# WS2812B.net
KiCad netlist of a schematic drawn in Altium Designer
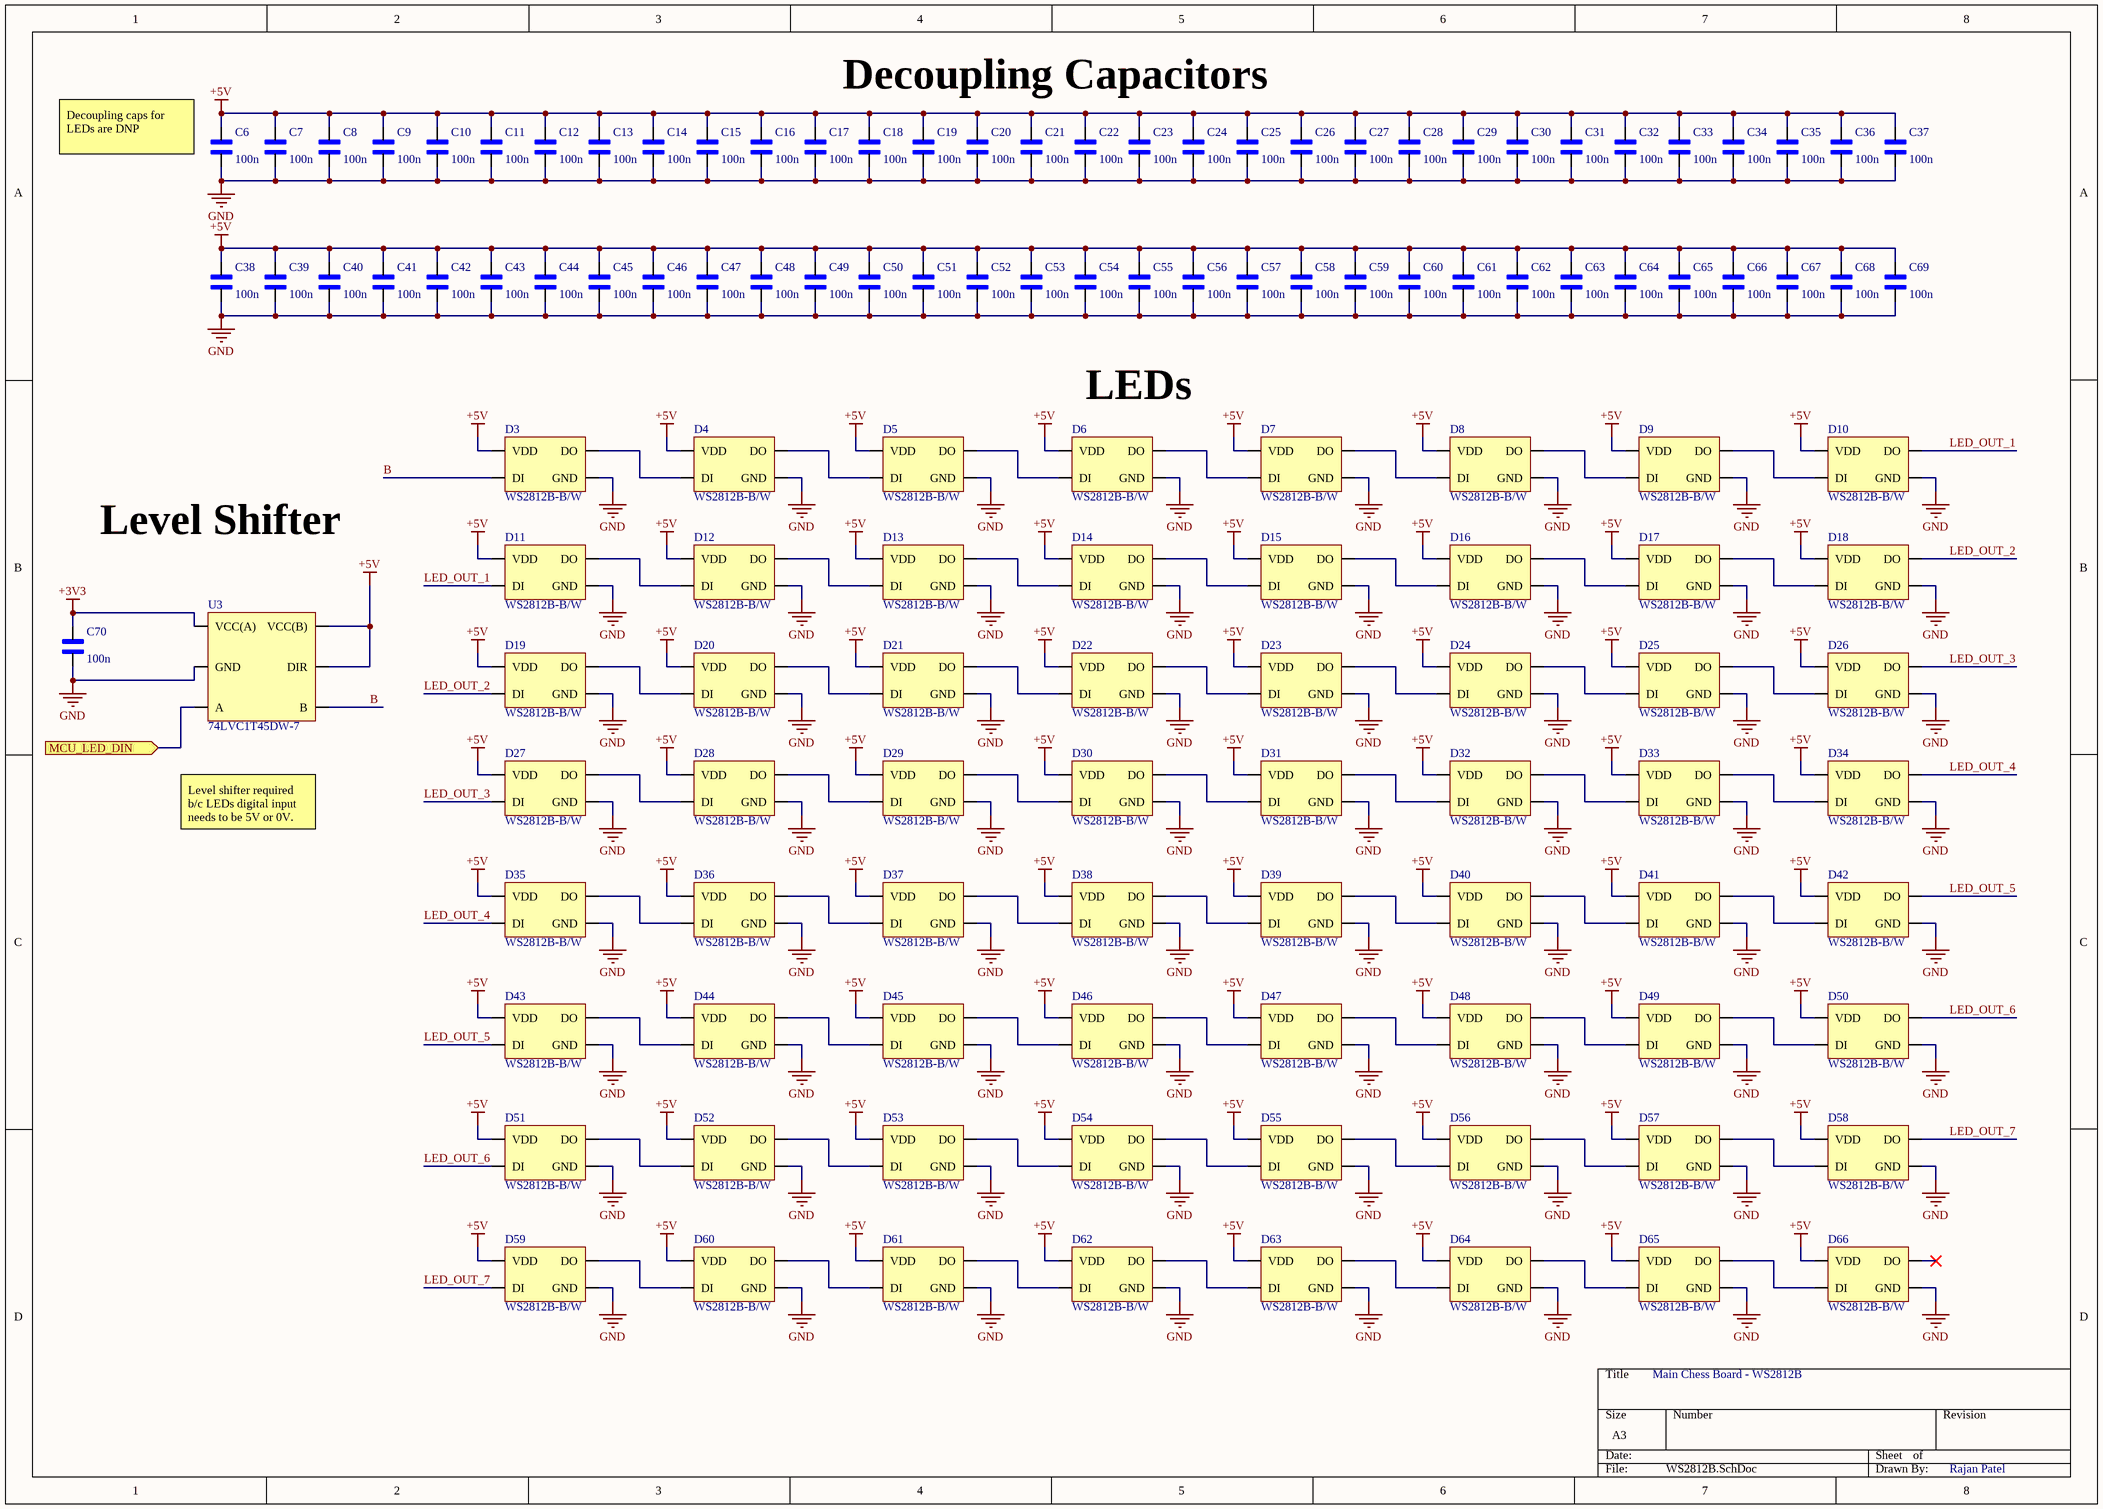
[diagram p0: WS2812B.SchDoc]

(export (version "E")
  (design (tool "Eeschema 10.0.6"))
  (components
    (comp (ref "C6")
      (value "100n")
      (footprint "CAP 0805")
      (libsource (lib "ChessBoardSchLib") (part "CAP 0805"))
    )
    (comp (ref "C7")
      (value "100n")
      (footprint "CAP 0805")
      (libsource (lib "ChessBoardSchLib") (part "CAP 0805"))
    )
    (comp (ref "C8")
      (value "100n")
      (footprint "CAP 0805")
      (libsource (lib "ChessBoardSchLib") (part "CAP 0805"))
    )
    (comp (ref "C9")
      (value "100n")
      (footprint "CAP 0805")
      (libsource (lib "ChessBoardSchLib") (part "CAP 0805"))
    )
    (comp (ref "C10")
      (value "100n")
      (footprint "CAP 0805")
      (libsource (lib "ChessBoardSchLib") (part "CAP 0805"))
    )
    (comp (ref "C11")
      (value "100n")
      (footprint "CAP 0805")
      (libsource (lib "ChessBoardSchLib") (part "CAP 0805"))
    )
    (comp (ref "C12")
      (value "100n")
      (footprint "CAP 0805")
      (libsource (lib "ChessBoardSchLib") (part "CAP 0805"))
    )
    (comp (ref "C13")
      (value "100n")
      (footprint "CAP 0805")
      (libsource (lib "ChessBoardSchLib") (part "CAP 0805"))
    )
    (comp (ref "C14")
      (value "100n")
      (footprint "CAP 0805")
      (libsource (lib "ChessBoardSchLib") (part "CAP 0805"))
    )
    (comp (ref "C15")
      (value "100n")
      (footprint "CAP 0805")
      (libsource (lib "ChessBoardSchLib") (part "CAP 0805"))
    )
    (comp (ref "C16")
      (value "100n")
      (footprint "CAP 0805")
      (libsource (lib "ChessBoardSchLib") (part "CAP 0805"))
    )
    (comp (ref "C17")
      (value "100n")
      (footprint "CAP 0805")
      (libsource (lib "ChessBoardSchLib") (part "CAP 0805"))
    )
    (comp (ref "C18")
      (value "100n")
      (footprint "CAP 0805")
      (libsource (lib "ChessBoardSchLib") (part "CAP 0805"))
    )
    (comp (ref "C19")
      (value "100n")
      (footprint "CAP 0805")
      (libsource (lib "ChessBoardSchLib") (part "CAP 0805"))
    )
    (comp (ref "C20")
      (value "100n")
      (footprint "CAP 0805")
      (libsource (lib "ChessBoardSchLib") (part "CAP 0805"))
    )
    (comp (ref "C21")
      (value "100n")
      (footprint "CAP 0805")
      (libsource (lib "ChessBoardSchLib") (part "CAP 0805"))
    )
    (comp (ref "C22")
      (value "100n")
      (footprint "CAP 0805")
      (libsource (lib "ChessBoardSchLib") (part "CAP 0805"))
    )
    (comp (ref "C23")
      (value "100n")
      (footprint "CAP 0805")
      (libsource (lib "ChessBoardSchLib") (part "CAP 0805"))
    )
    (comp (ref "C24")
      (value "100n")
      (footprint "CAP 0805")
      (libsource (lib "ChessBoardSchLib") (part "CAP 0805"))
    )
    (comp (ref "C25")
      (value "100n")
      (footprint "CAP 0805")
      (libsource (lib "ChessBoardSchLib") (part "CAP 0805"))
    )
    (comp (ref "C26")
      (value "100n")
      (footprint "CAP 0805")
      (libsource (lib "ChessBoardSchLib") (part "CAP 0805"))
    )
    (comp (ref "C27")
      (value "100n")
      (footprint "CAP 0805")
      (libsource (lib "ChessBoardSchLib") (part "CAP 0805"))
    )
    (comp (ref "C28")
      (value "100n")
      (footprint "CAP 0805")
      (libsource (lib "ChessBoardSchLib") (part "CAP 0805"))
    )
    (comp (ref "C29")
      (value "100n")
      (footprint "CAP 0805")
      (libsource (lib "ChessBoardSchLib") (part "CAP 0805"))
    )
    (comp (ref "C30")
      (value "100n")
      (footprint "CAP 0805")
      (libsource (lib "ChessBoardSchLib") (part "CAP 0805"))
    )
    (comp (ref "C31")
      (value "100n")
      (footprint "CAP 0805")
      (libsource (lib "ChessBoardSchLib") (part "CAP 0805"))
    )
    (comp (ref "C32")
      (value "100n")
      (footprint "CAP 0805")
      (libsource (lib "ChessBoardSchLib") (part "CAP 0805"))
    )
    (comp (ref "C33")
      (value "100n")
      (footprint "CAP 0805")
      (libsource (lib "ChessBoardSchLib") (part "CAP 0805"))
    )
    (comp (ref "C34")
      (value "100n")
      (footprint "CAP 0805")
      (libsource (lib "ChessBoardSchLib") (part "CAP 0805"))
    )
    (comp (ref "C35")
      (value "100n")
      (footprint "CAP 0805")
      (libsource (lib "ChessBoardSchLib") (part "CAP 0805"))
    )
    (comp (ref "C36")
      (value "100n")
      (footprint "CAP 0805")
      (libsource (lib "ChessBoardSchLib") (part "CAP 0805"))
    )
    (comp (ref "C37")
      (value "100n")
      (footprint "CAP 0805")
      (libsource (lib "ChessBoardSchLib") (part "CAP 0805"))
    )
    (comp (ref "C38")
      (value "100n")
      (footprint "CAP 0805")
      (libsource (lib "ChessBoardSchLib") (part "CAP 0805"))
    )
    (comp (ref "C39")
      (value "100n")
      (footprint "CAP 0805")
      (libsource (lib "ChessBoardSchLib") (part "CAP 0805"))
    )
    (comp (ref "C40")
      (value "100n")
      (footprint "CAP 0805")
      (libsource (lib "ChessBoardSchLib") (part "CAP 0805"))
    )
    (comp (ref "C41")
      (value "100n")
      (footprint "CAP 0805")
      (libsource (lib "ChessBoardSchLib") (part "CAP 0805"))
    )
    (comp (ref "C42")
      (value "100n")
      (footprint "CAP 0805")
      (libsource (lib "ChessBoardSchLib") (part "CAP 0805"))
    )
    (comp (ref "C43")
      (value "100n")
      (footprint "CAP 0805")
      (libsource (lib "ChessBoardSchLib") (part "CAP 0805"))
    )
    (comp (ref "C44")
      (value "100n")
      (footprint "CAP 0805")
      (libsource (lib "ChessBoardSchLib") (part "CAP 0805"))
    )
    (comp (ref "C45")
      (value "100n")
      (footprint "CAP 0805")
      (libsource (lib "ChessBoardSchLib") (part "CAP 0805"))
    )
    (comp (ref "C46")
      (value "100n")
      (footprint "CAP 0805")
      (libsource (lib "ChessBoardSchLib") (part "CAP 0805"))
    )
    (comp (ref "C47")
      (value "100n")
      (footprint "CAP 0805")
      (libsource (lib "ChessBoardSchLib") (part "CAP 0805"))
    )
    (comp (ref "C48")
      (value "100n")
      (footprint "CAP 0805")
      (libsource (lib "ChessBoardSchLib") (part "CAP 0805"))
    )
    (comp (ref "C49")
      (value "100n")
      (footprint "CAP 0805")
      (libsource (lib "ChessBoardSchLib") (part "CAP 0805"))
    )
    (comp (ref "C50")
      (value "100n")
      (footprint "CAP 0805")
      (libsource (lib "ChessBoardSchLib") (part "CAP 0805"))
    )
    (comp (ref "C51")
      (value "100n")
      (footprint "CAP 0805")
      (libsource (lib "ChessBoardSchLib") (part "CAP 0805"))
    )
    (comp (ref "C52")
      (value "100n")
      (footprint "CAP 0805")
      (libsource (lib "ChessBoardSchLib") (part "CAP 0805"))
    )
    (comp (ref "C53")
      (value "100n")
      (footprint "CAP 0805")
      (libsource (lib "ChessBoardSchLib") (part "CAP 0805"))
    )
    (comp (ref "C54")
      (value "100n")
      (footprint "CAP 0805")
      (libsource (lib "ChessBoardSchLib") (part "CAP 0805"))
    )
    (comp (ref "C55")
      (value "100n")
      (footprint "CAP 0805")
      (libsource (lib "ChessBoardSchLib") (part "CAP 0805"))
    )
    (comp (ref "C56")
      (value "100n")
      (footprint "CAP 0805")
      (libsource (lib "ChessBoardSchLib") (part "CAP 0805"))
    )
    (comp (ref "C57")
      (value "100n")
      (footprint "CAP 0805")
      (libsource (lib "ChessBoardSchLib") (part "CAP 0805"))
    )
    (comp (ref "C58")
      (value "100n")
      (footprint "CAP 0805")
      (libsource (lib "ChessBoardSchLib") (part "CAP 0805"))
    )
    (comp (ref "C59")
      (value "100n")
      (footprint "CAP 0805")
      (libsource (lib "ChessBoardSchLib") (part "CAP 0805"))
    )
    (comp (ref "C60")
      (value "100n")
      (footprint "CAP 0805")
      (libsource (lib "ChessBoardSchLib") (part "CAP 0805"))
    )
    (comp (ref "C61")
      (value "100n")
      (footprint "CAP 0805")
      (libsource (lib "ChessBoardSchLib") (part "CAP 0805"))
    )
    (comp (ref "C62")
      (value "100n")
      (footprint "CAP 0805")
      (libsource (lib "ChessBoardSchLib") (part "CAP 0805"))
    )
    (comp (ref "C63")
      (value "100n")
      (footprint "CAP 0805")
      (libsource (lib "ChessBoardSchLib") (part "CAP 0805"))
    )
    (comp (ref "C64")
      (value "100n")
      (footprint "CAP 0805")
      (libsource (lib "ChessBoardSchLib") (part "CAP 0805"))
    )
    (comp (ref "C65")
      (value "100n")
      (footprint "CAP 0805")
      (libsource (lib "ChessBoardSchLib") (part "CAP 0805"))
    )
    (comp (ref "C66")
      (value "100n")
      (footprint "CAP 0805")
      (libsource (lib "ChessBoardSchLib") (part "CAP 0805"))
    )
    (comp (ref "C67")
      (value "100n")
      (footprint "CAP 0805")
      (libsource (lib "ChessBoardSchLib") (part "CAP 0805"))
    )
    (comp (ref "C68")
      (value "100n")
      (footprint "CAP 0805")
      (libsource (lib "ChessBoardSchLib") (part "CAP 0805"))
    )
    (comp (ref "C69")
      (value "100n")
      (footprint "CAP 0805")
      (libsource (lib "ChessBoardSchLib") (part "CAP 0805"))
    )
    (comp (ref "C70")
      (value "100n")
      (footprint "CAP 0805")
      (libsource (lib "ChessBoardSchLib") (part "CAP 0805"))
    )
    (comp (ref "D3")
      (value "WS2812B-B/W")
      (footprint "WS2812B-B/W")
      (description "SMD5050 RGB LEDs(Built-in IC) ROHS")
      (fields (field (name "MANUFACTURER") "Worldsemi"))
      (libsource (lib "ChessBoardSchLib") (part "WS2812B-B/W"))
    )
    (comp (ref "D4")
      (value "WS2812B-B/W")
      (footprint "WS2812B-B/W")
      (description "SMD5050 RGB LEDs(Built-in IC) ROHS")
      (fields (field (name "MANUFACTURER") "Worldsemi"))
      (libsource (lib "ChessBoardSchLib") (part "WS2812B-B/W"))
    )
    (comp (ref "D5")
      (value "WS2812B-B/W")
      (footprint "WS2812B-B/W")
      (description "SMD5050 RGB LEDs(Built-in IC) ROHS")
      (fields (field (name "MANUFACTURER") "Worldsemi"))
      (libsource (lib "ChessBoardSchLib") (part "WS2812B-B/W"))
    )
    (comp (ref "D6")
      (value "WS2812B-B/W")
      (footprint "WS2812B-B/W")
      (description "SMD5050 RGB LEDs(Built-in IC) ROHS")
      (fields (field (name "MANUFACTURER") "Worldsemi"))
      (libsource (lib "ChessBoardSchLib") (part "WS2812B-B/W"))
    )
    (comp (ref "D7")
      (value "WS2812B-B/W")
      (footprint "WS2812B-B/W")
      (description "SMD5050 RGB LEDs(Built-in IC) ROHS")
      (fields (field (name "MANUFACTURER") "Worldsemi"))
      (libsource (lib "ChessBoardSchLib") (part "WS2812B-B/W"))
    )
    (comp (ref "D8")
      (value "WS2812B-B/W")
      (footprint "WS2812B-B/W")
      (description "SMD5050 RGB LEDs(Built-in IC) ROHS")
      (fields (field (name "MANUFACTURER") "Worldsemi"))
      (libsource (lib "ChessBoardSchLib") (part "WS2812B-B/W"))
    )
    (comp (ref "D9")
      (value "WS2812B-B/W")
      (footprint "WS2812B-B/W")
      (description "SMD5050 RGB LEDs(Built-in IC) ROHS")
      (fields (field (name "MANUFACTURER") "Worldsemi"))
      (libsource (lib "ChessBoardSchLib") (part "WS2812B-B/W"))
    )
    (comp (ref "D10")
      (value "WS2812B-B/W")
      (footprint "WS2812B-B/W")
      (description "SMD5050 RGB LEDs(Built-in IC) ROHS")
      (fields (field (name "MANUFACTURER") "Worldsemi"))
      (libsource (lib "ChessBoardSchLib") (part "WS2812B-B/W"))
    )
    (comp (ref "D11")
      (value "WS2812B-B/W")
      (footprint "WS2812B-B/W")
      (description "SMD5050 RGB LEDs(Built-in IC) ROHS")
      (fields (field (name "MANUFACTURER") "Worldsemi"))
      (libsource (lib "ChessBoardSchLib") (part "WS2812B-B/W"))
    )
    (comp (ref "D12")
      (value "WS2812B-B/W")
      (footprint "WS2812B-B/W")
      (description "SMD5050 RGB LEDs(Built-in IC) ROHS")
      (fields (field (name "MANUFACTURER") "Worldsemi"))
      (libsource (lib "ChessBoardSchLib") (part "WS2812B-B/W"))
    )
    (comp (ref "D13")
      (value "WS2812B-B/W")
      (footprint "WS2812B-B/W")
      (description "SMD5050 RGB LEDs(Built-in IC) ROHS")
      (fields (field (name "MANUFACTURER") "Worldsemi"))
      (libsource (lib "ChessBoardSchLib") (part "WS2812B-B/W"))
    )
    (comp (ref "D14")
      (value "WS2812B-B/W")
      (footprint "WS2812B-B/W")
      (description "SMD5050 RGB LEDs(Built-in IC) ROHS")
      (fields (field (name "MANUFACTURER") "Worldsemi"))
      (libsource (lib "ChessBoardSchLib") (part "WS2812B-B/W"))
    )
    (comp (ref "D15")
      (value "WS2812B-B/W")
      (footprint "WS2812B-B/W")
      (description "SMD5050 RGB LEDs(Built-in IC) ROHS")
      (fields (field (name "MANUFACTURER") "Worldsemi"))
      (libsource (lib "ChessBoardSchLib") (part "WS2812B-B/W"))
    )
    (comp (ref "D16")
      (value "WS2812B-B/W")
      (footprint "WS2812B-B/W")
      (description "SMD5050 RGB LEDs(Built-in IC) ROHS")
      (fields (field (name "MANUFACTURER") "Worldsemi"))
      (libsource (lib "ChessBoardSchLib") (part "WS2812B-B/W"))
    )
    (comp (ref "D17")
      (value "WS2812B-B/W")
      (footprint "WS2812B-B/W")
      (description "SMD5050 RGB LEDs(Built-in IC) ROHS")
      (fields (field (name "MANUFACTURER") "Worldsemi"))
      (libsource (lib "ChessBoardSchLib") (part "WS2812B-B/W"))
    )
    (comp (ref "D18")
      (value "WS2812B-B/W")
      (footprint "WS2812B-B/W")
      (description "SMD5050 RGB LEDs(Built-in IC) ROHS")
      (fields (field (name "MANUFACTURER") "Worldsemi"))
      (libsource (lib "ChessBoardSchLib") (part "WS2812B-B/W"))
    )
    (comp (ref "D19")
      (value "WS2812B-B/W")
      (footprint "WS2812B-B/W")
      (description "SMD5050 RGB LEDs(Built-in IC) ROHS")
      (fields (field (name "MANUFACTURER") "Worldsemi"))
      (libsource (lib "ChessBoardSchLib") (part "WS2812B-B/W"))
    )
    (comp (ref "D20")
      (value "WS2812B-B/W")
      (footprint "WS2812B-B/W")
      (description "SMD5050 RGB LEDs(Built-in IC) ROHS")
      (fields (field (name "MANUFACTURER") "Worldsemi"))
      (libsource (lib "ChessBoardSchLib") (part "WS2812B-B/W"))
    )
    (comp (ref "D21")
      (value "WS2812B-B/W")
      (footprint "WS2812B-B/W")
      (description "SMD5050 RGB LEDs(Built-in IC) ROHS")
      (fields (field (name "MANUFACTURER") "Worldsemi"))
      (libsource (lib "ChessBoardSchLib") (part "WS2812B-B/W"))
    )
    (comp (ref "D22")
      (value "WS2812B-B/W")
      (footprint "WS2812B-B/W")
      (description "SMD5050 RGB LEDs(Built-in IC) ROHS")
      (fields (field (name "MANUFACTURER") "Worldsemi"))
      (libsource (lib "ChessBoardSchLib") (part "WS2812B-B/W"))
    )
    (comp (ref "D23")
      (value "WS2812B-B/W")
      (footprint "WS2812B-B/W")
      (description "SMD5050 RGB LEDs(Built-in IC) ROHS")
      (fields (field (name "MANUFACTURER") "Worldsemi"))
      (libsource (lib "ChessBoardSchLib") (part "WS2812B-B/W"))
    )
    (comp (ref "D24")
      (value "WS2812B-B/W")
      (footprint "WS2812B-B/W")
      (description "SMD5050 RGB LEDs(Built-in IC) ROHS")
      (fields (field (name "MANUFACTURER") "Worldsemi"))
      (libsource (lib "ChessBoardSchLib") (part "WS2812B-B/W"))
    )
    (comp (ref "D25")
      (value "WS2812B-B/W")
      (footprint "WS2812B-B/W")
      (description "SMD5050 RGB LEDs(Built-in IC) ROHS")
      (fields (field (name "MANUFACTURER") "Worldsemi"))
      (libsource (lib "ChessBoardSchLib") (part "WS2812B-B/W"))
    )
    (comp (ref "D26")
      (value "WS2812B-B/W")
      (footprint "WS2812B-B/W")
      (description "SMD5050 RGB LEDs(Built-in IC) ROHS")
      (fields (field (name "MANUFACTURER") "Worldsemi"))
      (libsource (lib "ChessBoardSchLib") (part "WS2812B-B/W"))
    )
    (comp (ref "D27")
      (value "WS2812B-B/W")
      (footprint "WS2812B-B/W")
      (description "SMD5050 RGB LEDs(Built-in IC) ROHS")
      (fields (field (name "MANUFACTURER") "Worldsemi"))
      (libsource (lib "ChessBoardSchLib") (part "WS2812B-B/W"))
    )
    (comp (ref "D28")
      (value "WS2812B-B/W")
      (footprint "WS2812B-B/W")
      (description "SMD5050 RGB LEDs(Built-in IC) ROHS")
      (fields (field (name "MANUFACTURER") "Worldsemi"))
      (libsource (lib "ChessBoardSchLib") (part "WS2812B-B/W"))
    )
    (comp (ref "D29")
      (value "WS2812B-B/W")
      (footprint "WS2812B-B/W")
      (description "SMD5050 RGB LEDs(Built-in IC) ROHS")
      (fields (field (name "MANUFACTURER") "Worldsemi"))
      (libsource (lib "ChessBoardSchLib") (part "WS2812B-B/W"))
    )
    (comp (ref "D30")
      (value "WS2812B-B/W")
      (footprint "WS2812B-B/W")
      (description "SMD5050 RGB LEDs(Built-in IC) ROHS")
      (fields (field (name "MANUFACTURER") "Worldsemi"))
      (libsource (lib "ChessBoardSchLib") (part "WS2812B-B/W"))
    )
    (comp (ref "D31")
      (value "WS2812B-B/W")
      (footprint "WS2812B-B/W")
      (description "SMD5050 RGB LEDs(Built-in IC) ROHS")
      (fields (field (name "MANUFACTURER") "Worldsemi"))
      (libsource (lib "ChessBoardSchLib") (part "WS2812B-B/W"))
    )
    (comp (ref "D32")
      (value "WS2812B-B/W")
      (footprint "WS2812B-B/W")
      (description "SMD5050 RGB LEDs(Built-in IC) ROHS")
      (fields (field (name "MANUFACTURER") "Worldsemi"))
      (libsource (lib "ChessBoardSchLib") (part "WS2812B-B/W"))
    )
    (comp (ref "D33")
      (value "WS2812B-B/W")
      (footprint "WS2812B-B/W")
      (description "SMD5050 RGB LEDs(Built-in IC) ROHS")
      (fields (field (name "MANUFACTURER") "Worldsemi"))
      (libsource (lib "ChessBoardSchLib") (part "WS2812B-B/W"))
    )
    (comp (ref "D34")
      (value "WS2812B-B/W")
      (footprint "WS2812B-B/W")
      (description "SMD5050 RGB LEDs(Built-in IC) ROHS")
      (fields (field (name "MANUFACTURER") "Worldsemi"))
      (libsource (lib "ChessBoardSchLib") (part "WS2812B-B/W"))
    )
    (comp (ref "D35")
      (value "WS2812B-B/W")
      (footprint "WS2812B-B/W")
      (description "SMD5050 RGB LEDs(Built-in IC) ROHS")
      (fields (field (name "MANUFACTURER") "Worldsemi"))
      (libsource (lib "ChessBoardSchLib") (part "WS2812B-B/W"))
    )
    (comp (ref "D36")
      (value "WS2812B-B/W")
      (footprint "WS2812B-B/W")
      (description "SMD5050 RGB LEDs(Built-in IC) ROHS")
      (fields (field (name "MANUFACTURER") "Worldsemi"))
      (libsource (lib "ChessBoardSchLib") (part "WS2812B-B/W"))
    )
    (comp (ref "D37")
      (value "WS2812B-B/W")
      (footprint "WS2812B-B/W")
      (description "SMD5050 RGB LEDs(Built-in IC) ROHS")
      (fields (field (name "MANUFACTURER") "Worldsemi"))
      (libsource (lib "ChessBoardSchLib") (part "WS2812B-B/W"))
    )
    (comp (ref "D38")
      (value "WS2812B-B/W")
      (footprint "WS2812B-B/W")
      (description "SMD5050 RGB LEDs(Built-in IC) ROHS")
      (fields (field (name "MANUFACTURER") "Worldsemi"))
      (libsource (lib "ChessBoardSchLib") (part "WS2812B-B/W"))
    )
    (comp (ref "D39")
      (value "WS2812B-B/W")
      (footprint "WS2812B-B/W")
      (description "SMD5050 RGB LEDs(Built-in IC) ROHS")
      (fields (field (name "MANUFACTURER") "Worldsemi"))
      (libsource (lib "ChessBoardSchLib") (part "WS2812B-B/W"))
    )
    (comp (ref "D40")
      (value "WS2812B-B/W")
      (footprint "WS2812B-B/W")
      (description "SMD5050 RGB LEDs(Built-in IC) ROHS")
      (fields (field (name "MANUFACTURER") "Worldsemi"))
      (libsource (lib "ChessBoardSchLib") (part "WS2812B-B/W"))
    )
    (comp (ref "D41")
      (value "WS2812B-B/W")
      (footprint "WS2812B-B/W")
      (description "SMD5050 RGB LEDs(Built-in IC) ROHS")
      (fields (field (name "MANUFACTURER") "Worldsemi"))
      (libsource (lib "ChessBoardSchLib") (part "WS2812B-B/W"))
    )
    (comp (ref "D42")
      (value "WS2812B-B/W")
      (footprint "WS2812B-B/W")
      (description "SMD5050 RGB LEDs(Built-in IC) ROHS")
      (fields (field (name "MANUFACTURER") "Worldsemi"))
      (libsource (lib "ChessBoardSchLib") (part "WS2812B-B/W"))
    )
    (comp (ref "D43")
      (value "WS2812B-B/W")
      (footprint "WS2812B-B/W")
      (description "SMD5050 RGB LEDs(Built-in IC) ROHS")
      (fields (field (name "MANUFACTURER") "Worldsemi"))
      (libsource (lib "ChessBoardSchLib") (part "WS2812B-B/W"))
    )
    (comp (ref "D44")
      (value "WS2812B-B/W")
      (footprint "WS2812B-B/W")
      (description "SMD5050 RGB LEDs(Built-in IC) ROHS")
      (fields (field (name "MANUFACTURER") "Worldsemi"))
      (libsource (lib "ChessBoardSchLib") (part "WS2812B-B/W"))
    )
    (comp (ref "D45")
      (value "WS2812B-B/W")
      (footprint "WS2812B-B/W")
      (description "SMD5050 RGB LEDs(Built-in IC) ROHS")
      (fields (field (name "MANUFACTURER") "Worldsemi"))
      (libsource (lib "ChessBoardSchLib") (part "WS2812B-B/W"))
    )
    (comp (ref "D46")
      (value "WS2812B-B/W")
      (footprint "WS2812B-B/W")
      (description "SMD5050 RGB LEDs(Built-in IC) ROHS")
      (fields (field (name "MANUFACTURER") "Worldsemi"))
      (libsource (lib "ChessBoardSchLib") (part "WS2812B-B/W"))
    )
    (comp (ref "D47")
      (value "WS2812B-B/W")
      (footprint "WS2812B-B/W")
      (description "SMD5050 RGB LEDs(Built-in IC) ROHS")
      (fields (field (name "MANUFACTURER") "Worldsemi"))
      (libsource (lib "ChessBoardSchLib") (part "WS2812B-B/W"))
    )
    (comp (ref "D48")
      (value "WS2812B-B/W")
      (footprint "WS2812B-B/W")
      (description "SMD5050 RGB LEDs(Built-in IC) ROHS")
      (fields (field (name "MANUFACTURER") "Worldsemi"))
      (libsource (lib "ChessBoardSchLib") (part "WS2812B-B/W"))
    )
    (comp (ref "D49")
      (value "WS2812B-B/W")
      (footprint "WS2812B-B/W")
      (description "SMD5050 RGB LEDs(Built-in IC) ROHS")
      (fields (field (name "MANUFACTURER") "Worldsemi"))
      (libsource (lib "ChessBoardSchLib") (part "WS2812B-B/W"))
    )
    (comp (ref "D50")
      (value "WS2812B-B/W")
      (footprint "WS2812B-B/W")
      (description "SMD5050 RGB LEDs(Built-in IC) ROHS")
      (fields (field (name "MANUFACTURER") "Worldsemi"))
      (libsource (lib "ChessBoardSchLib") (part "WS2812B-B/W"))
    )
    (comp (ref "D51")
      (value "WS2812B-B/W")
      (footprint "WS2812B-B/W")
      (description "SMD5050 RGB LEDs(Built-in IC) ROHS")
      (fields (field (name "MANUFACTURER") "Worldsemi"))
      (libsource (lib "ChessBoardSchLib") (part "WS2812B-B/W"))
    )
    (comp (ref "D52")
      (value "WS2812B-B/W")
      (footprint "WS2812B-B/W")
      (description "SMD5050 RGB LEDs(Built-in IC) ROHS")
      (fields (field (name "MANUFACTURER") "Worldsemi"))
      (libsource (lib "ChessBoardSchLib") (part "WS2812B-B/W"))
    )
    (comp (ref "D53")
      (value "WS2812B-B/W")
      (footprint "WS2812B-B/W")
      (description "SMD5050 RGB LEDs(Built-in IC) ROHS")
      (fields (field (name "MANUFACTURER") "Worldsemi"))
      (libsource (lib "ChessBoardSchLib") (part "WS2812B-B/W"))
    )
    (comp (ref "D54")
      (value "WS2812B-B/W")
      (footprint "WS2812B-B/W")
      (description "SMD5050 RGB LEDs(Built-in IC) ROHS")
      (fields (field (name "MANUFACTURER") "Worldsemi"))
      (libsource (lib "ChessBoardSchLib") (part "WS2812B-B/W"))
    )
    (comp (ref "D55")
      (value "WS2812B-B/W")
      (footprint "WS2812B-B/W")
      (description "SMD5050 RGB LEDs(Built-in IC) ROHS")
      (fields (field (name "MANUFACTURER") "Worldsemi"))
      (libsource (lib "ChessBoardSchLib") (part "WS2812B-B/W"))
    )
    (comp (ref "D56")
      (value "WS2812B-B/W")
      (footprint "WS2812B-B/W")
      (description "SMD5050 RGB LEDs(Built-in IC) ROHS")
      (fields (field (name "MANUFACTURER") "Worldsemi"))
      (libsource (lib "ChessBoardSchLib") (part "WS2812B-B/W"))
    )
    (comp (ref "D57")
      (value "WS2812B-B/W")
      (footprint "WS2812B-B/W")
      (description "SMD5050 RGB LEDs(Built-in IC) ROHS")
      (fields (field (name "MANUFACTURER") "Worldsemi"))
      (libsource (lib "ChessBoardSchLib") (part "WS2812B-B/W"))
    )
    (comp (ref "D58")
      (value "WS2812B-B/W")
      (footprint "WS2812B-B/W")
      (description "SMD5050 RGB LEDs(Built-in IC) ROHS")
      (fields (field (name "MANUFACTURER") "Worldsemi"))
      (libsource (lib "ChessBoardSchLib") (part "WS2812B-B/W"))
    )
    (comp (ref "D59")
      (value "WS2812B-B/W")
      (footprint "WS2812B-B/W")
      (description "SMD5050 RGB LEDs(Built-in IC) ROHS")
      (fields (field (name "MANUFACTURER") "Worldsemi"))
      (libsource (lib "ChessBoardSchLib") (part "WS2812B-B/W"))
    )
    (comp (ref "D60")
      (value "WS2812B-B/W")
      (footprint "WS2812B-B/W")
      (description "SMD5050 RGB LEDs(Built-in IC) ROHS")
      (fields (field (name "MANUFACTURER") "Worldsemi"))
      (libsource (lib "ChessBoardSchLib") (part "WS2812B-B/W"))
    )
    (comp (ref "D61")
      (value "WS2812B-B/W")
      (footprint "WS2812B-B/W")
      (description "SMD5050 RGB LEDs(Built-in IC) ROHS")
      (fields (field (name "MANUFACTURER") "Worldsemi"))
      (libsource (lib "ChessBoardSchLib") (part "WS2812B-B/W"))
    )
    (comp (ref "D62")
      (value "WS2812B-B/W")
      (footprint "WS2812B-B/W")
      (description "SMD5050 RGB LEDs(Built-in IC) ROHS")
      (fields (field (name "MANUFACTURER") "Worldsemi"))
      (libsource (lib "ChessBoardSchLib") (part "WS2812B-B/W"))
    )
    (comp (ref "D63")
      (value "WS2812B-B/W")
      (footprint "WS2812B-B/W")
      (description "SMD5050 RGB LEDs(Built-in IC) ROHS")
      (fields (field (name "MANUFACTURER") "Worldsemi"))
      (libsource (lib "ChessBoardSchLib") (part "WS2812B-B/W"))
    )
    (comp (ref "D64")
      (value "WS2812B-B/W")
      (footprint "WS2812B-B/W")
      (description "SMD5050 RGB LEDs(Built-in IC) ROHS")
      (fields (field (name "MANUFACTURER") "Worldsemi"))
      (libsource (lib "ChessBoardSchLib") (part "WS2812B-B/W"))
    )
    (comp (ref "D65")
      (value "WS2812B-B/W")
      (footprint "WS2812B-B/W")
      (description "SMD5050 RGB LEDs(Built-in IC) ROHS")
      (fields (field (name "MANUFACTURER") "Worldsemi"))
      (libsource (lib "ChessBoardSchLib") (part "WS2812B-B/W"))
    )
    (comp (ref "D66")
      (value "WS2812B-B/W")
      (footprint "WS2812B-B/W")
      (description "SMD5050 RGB LEDs(Built-in IC) ROHS")
      (fields (field (name "MANUFACTURER") "Worldsemi"))
      (libsource (lib "ChessBoardSchLib") (part "WS2812B-B/W"))
    )
    (comp (ref "U3")
      (value "74LVC1T45DW-7")
      (footprint "74LVC1T45DW-7")
      (description "Bus Transceiver, LVC/LCX/Z Series, 1-Func, 1-Bit, True Output, CMOS, PDSO6")
      (fields (field (name "MANUFACTURER") "Diodes"))
      (libsource (lib "ChessBoardSchLib") (part "74LVC1T45DW-7"))
    )
  )
  (nets
    (net (code "1") (name "+3V3") (class "Default")
      (node (ref "C70") (pin "2") (pinfunction "2_2") (pintype "passive"))
      (node (ref "U3") (pin "1") (pinfunction "VCC(A)_1") (pintype "passive"))
    )
    (net (code "2") (name "+5V") (class "Default")
      (node (ref "C10") (pin "2") (pinfunction "2_2") (pintype "passive"))
      (node (ref "C11") (pin "2") (pinfunction "2_2") (pintype "passive"))
      (node (ref "C12") (pin "2") (pinfunction "2_2") (pintype "passive"))
      (node (ref "C13") (pin "2") (pinfunction "2_2") (pintype "passive"))
      (node (ref "C14") (pin "2") (pinfunction "2_2") (pintype "passive"))
      (node (ref "C15") (pin "2") (pinfunction "2_2") (pintype "passive"))
      (node (ref "C16") (pin "2") (pinfunction "2_2") (pintype "passive"))
      (node (ref "C17") (pin "2") (pinfunction "2_2") (pintype "passive"))
      (node (ref "C18") (pin "2") (pinfunction "2_2") (pintype "passive"))
      (node (ref "C19") (pin "2") (pinfunction "2_2") (pintype "passive"))
      (node (ref "C20") (pin "2") (pinfunction "2_2") (pintype "passive"))
      (node (ref "C21") (pin "2") (pinfunction "2_2") (pintype "passive"))
      (node (ref "C22") (pin "2") (pinfunction "2_2") (pintype "passive"))
      (node (ref "C23") (pin "2") (pinfunction "2_2") (pintype "passive"))
      (node (ref "C24") (pin "2") (pinfunction "2_2") (pintype "passive"))
      (node (ref "C25") (pin "2") (pinfunction "2_2") (pintype "passive"))
      (node (ref "C26") (pin "2") (pinfunction "2_2") (pintype "passive"))
      (node (ref "C27") (pin "2") (pinfunction "2_2") (pintype "passive"))
      (node (ref "C28") (pin "2") (pinfunction "2_2") (pintype "passive"))
      (node (ref "C29") (pin "2") (pinfunction "2_2") (pintype "passive"))
      (node (ref "C30") (pin "2") (pinfunction "2_2") (pintype "passive"))
      (node (ref "C31") (pin "2") (pinfunction "2_2") (pintype "passive"))
      (node (ref "C32") (pin "2") (pinfunction "2_2") (pintype "passive"))
      (node (ref "C33") (pin "2") (pinfunction "2_2") (pintype "passive"))
      (node (ref "C34") (pin "2") (pinfunction "2_2") (pintype "passive"))
      (node (ref "C35") (pin "2") (pinfunction "2_2") (pintype "passive"))
      (node (ref "C36") (pin "2") (pinfunction "2_2") (pintype "passive"))
      (node (ref "C37") (pin "2") (pinfunction "2_2") (pintype "passive"))
      (node (ref "C38") (pin "2") (pinfunction "2_2") (pintype "passive"))
      (node (ref "C39") (pin "2") (pinfunction "2_2") (pintype "passive"))
      (node (ref "C40") (pin "2") (pinfunction "2_2") (pintype "passive"))
      (node (ref "C41") (pin "2") (pinfunction "2_2") (pintype "passive"))
      (node (ref "C42") (pin "2") (pinfunction "2_2") (pintype "passive"))
      (node (ref "C43") (pin "2") (pinfunction "2_2") (pintype "passive"))
      (node (ref "C44") (pin "2") (pinfunction "2_2") (pintype "passive"))
      (node (ref "C45") (pin "2") (pinfunction "2_2") (pintype "passive"))
      (node (ref "C46") (pin "2") (pinfunction "2_2") (pintype "passive"))
      (node (ref "C47") (pin "2") (pinfunction "2_2") (pintype "passive"))
      (node (ref "C48") (pin "2") (pinfunction "2_2") (pintype "passive"))
      (node (ref "C49") (pin "2") (pinfunction "2_2") (pintype "passive"))
      (node (ref "C50") (pin "2") (pinfunction "2_2") (pintype "passive"))
      (node (ref "C51") (pin "2") (pinfunction "2_2") (pintype "passive"))
      (node (ref "C52") (pin "2") (pinfunction "2_2") (pintype "passive"))
      (node (ref "C53") (pin "2") (pinfunction "2_2") (pintype "passive"))
      (node (ref "C54") (pin "2") (pinfunction "2_2") (pintype "passive"))
      (node (ref "C55") (pin "2") (pinfunction "2_2") (pintype "passive"))
      (node (ref "C56") (pin "2") (pinfunction "2_2") (pintype "passive"))
      (node (ref "C57") (pin "2") (pinfunction "2_2") (pintype "passive"))
      (node (ref "C58") (pin "2") (pinfunction "2_2") (pintype "passive"))
      (node (ref "C59") (pin "2") (pinfunction "2_2") (pintype "passive"))
      (node (ref "C6") (pin "2") (pinfunction "2_2") (pintype "passive"))
      (node (ref "C60") (pin "2") (pinfunction "2_2") (pintype "passive"))
      (node (ref "C61") (pin "2") (pinfunction "2_2") (pintype "passive"))
      (node (ref "C62") (pin "2") (pinfunction "2_2") (pintype "passive"))
      (node (ref "C63") (pin "2") (pinfunction "2_2") (pintype "passive"))
      (node (ref "C64") (pin "2") (pinfunction "2_2") (pintype "passive"))
      (node (ref "C65") (pin "2") (pinfunction "2_2") (pintype "passive"))
      (node (ref "C66") (pin "2") (pinfunction "2_2") (pintype "passive"))
      (node (ref "C67") (pin "2") (pinfunction "2_2") (pintype "passive"))
      (node (ref "C68") (pin "2") (pinfunction "2_2") (pintype "passive"))
      (node (ref "C69") (pin "2") (pinfunction "2_2") (pintype "passive"))
      (node (ref "C7") (pin "2") (pinfunction "2_2") (pintype "passive"))
      (node (ref "C8") (pin "2") (pinfunction "2_2") (pintype "passive"))
      (node (ref "C9") (pin "2") (pinfunction "2_2") (pintype "passive"))
      (node (ref "D10") (pin "1") (pinfunction "VDD_1") (pintype "passive"))
      (node (ref "D11") (pin "1") (pinfunction "VDD_1") (pintype "passive"))
      (node (ref "D12") (pin "1") (pinfunction "VDD_1") (pintype "passive"))
      (node (ref "D13") (pin "1") (pinfunction "VDD_1") (pintype "passive"))
      (node (ref "D14") (pin "1") (pinfunction "VDD_1") (pintype "passive"))
      (node (ref "D15") (pin "1") (pinfunction "VDD_1") (pintype "passive"))
      (node (ref "D16") (pin "1") (pinfunction "VDD_1") (pintype "passive"))
      (node (ref "D17") (pin "1") (pinfunction "VDD_1") (pintype "passive"))
      (node (ref "D18") (pin "1") (pinfunction "VDD_1") (pintype "passive"))
      (node (ref "D19") (pin "1") (pinfunction "VDD_1") (pintype "passive"))
      (node (ref "D20") (pin "1") (pinfunction "VDD_1") (pintype "passive"))
      (node (ref "D21") (pin "1") (pinfunction "VDD_1") (pintype "passive"))
      (node (ref "D22") (pin "1") (pinfunction "VDD_1") (pintype "passive"))
      (node (ref "D23") (pin "1") (pinfunction "VDD_1") (pintype "passive"))
      (node (ref "D24") (pin "1") (pinfunction "VDD_1") (pintype "passive"))
      (node (ref "D25") (pin "1") (pinfunction "VDD_1") (pintype "passive"))
      (node (ref "D26") (pin "1") (pinfunction "VDD_1") (pintype "passive"))
      (node (ref "D27") (pin "1") (pinfunction "VDD_1") (pintype "passive"))
      (node (ref "D28") (pin "1") (pinfunction "VDD_1") (pintype "passive"))
      (node (ref "D29") (pin "1") (pinfunction "VDD_1") (pintype "passive"))
      (node (ref "D3") (pin "1") (pinfunction "VDD_1") (pintype "passive"))
      (node (ref "D30") (pin "1") (pinfunction "VDD_1") (pintype "passive"))
      (node (ref "D31") (pin "1") (pinfunction "VDD_1") (pintype "passive"))
      (node (ref "D32") (pin "1") (pinfunction "VDD_1") (pintype "passive"))
      (node (ref "D33") (pin "1") (pinfunction "VDD_1") (pintype "passive"))
      (node (ref "D34") (pin "1") (pinfunction "VDD_1") (pintype "passive"))
      (node (ref "D35") (pin "1") (pinfunction "VDD_1") (pintype "passive"))
      (node (ref "D36") (pin "1") (pinfunction "VDD_1") (pintype "passive"))
      (node (ref "D37") (pin "1") (pinfunction "VDD_1") (pintype "passive"))
      (node (ref "D38") (pin "1") (pinfunction "VDD_1") (pintype "passive"))
      (node (ref "D39") (pin "1") (pinfunction "VDD_1") (pintype "passive"))
      (node (ref "D4") (pin "1") (pinfunction "VDD_1") (pintype "passive"))
      (node (ref "D40") (pin "1") (pinfunction "VDD_1") (pintype "passive"))
      (node (ref "D41") (pin "1") (pinfunction "VDD_1") (pintype "passive"))
      (node (ref "D42") (pin "1") (pinfunction "VDD_1") (pintype "passive"))
      (node (ref "D43") (pin "1") (pinfunction "VDD_1") (pintype "passive"))
      (node (ref "D44") (pin "1") (pinfunction "VDD_1") (pintype "passive"))
      (node (ref "D45") (pin "1") (pinfunction "VDD_1") (pintype "passive"))
      (node (ref "D46") (pin "1") (pinfunction "VDD_1") (pintype "passive"))
      (node (ref "D47") (pin "1") (pinfunction "VDD_1") (pintype "passive"))
      (node (ref "D48") (pin "1") (pinfunction "VDD_1") (pintype "passive"))
      (node (ref "D49") (pin "1") (pinfunction "VDD_1") (pintype "passive"))
      (node (ref "D5") (pin "1") (pinfunction "VDD_1") (pintype "passive"))
      (node (ref "D50") (pin "1") (pinfunction "VDD_1") (pintype "passive"))
      (node (ref "D51") (pin "1") (pinfunction "VDD_1") (pintype "passive"))
      (node (ref "D52") (pin "1") (pinfunction "VDD_1") (pintype "passive"))
      (node (ref "D53") (pin "1") (pinfunction "VDD_1") (pintype "passive"))
      (node (ref "D54") (pin "1") (pinfunction "VDD_1") (pintype "passive"))
      (node (ref "D55") (pin "1") (pinfunction "VDD_1") (pintype "passive"))
      (node (ref "D56") (pin "1") (pinfunction "VDD_1") (pintype "passive"))
      (node (ref "D57") (pin "1") (pinfunction "VDD_1") (pintype "passive"))
      (node (ref "D58") (pin "1") (pinfunction "VDD_1") (pintype "passive"))
      (node (ref "D59") (pin "1") (pinfunction "VDD_1") (pintype "passive"))
      (node (ref "D6") (pin "1") (pinfunction "VDD_1") (pintype "passive"))
      (node (ref "D60") (pin "1") (pinfunction "VDD_1") (pintype "passive"))
      (node (ref "D61") (pin "1") (pinfunction "VDD_1") (pintype "passive"))
      (node (ref "D62") (pin "1") (pinfunction "VDD_1") (pintype "passive"))
      (node (ref "D63") (pin "1") (pinfunction "VDD_1") (pintype "passive"))
      (node (ref "D64") (pin "1") (pinfunction "VDD_1") (pintype "passive"))
      (node (ref "D65") (pin "1") (pinfunction "VDD_1") (pintype "passive"))
      (node (ref "D66") (pin "1") (pinfunction "VDD_1") (pintype "passive"))
      (node (ref "D7") (pin "1") (pinfunction "VDD_1") (pintype "passive"))
      (node (ref "D8") (pin "1") (pinfunction "VDD_1") (pintype "passive"))
      (node (ref "D9") (pin "1") (pinfunction "VDD_1") (pintype "passive"))
      (node (ref "U3") (pin "5") (pinfunction "DIR_5") (pintype "passive"))
      (node (ref "U3") (pin "6") (pinfunction "VCC(B)_6") (pintype "passive"))
    )
    (net (code "3") (name "/B") (class "Default")
      (node (ref "D3") (pin "2") (pinfunction "DI_2") (pintype "passive"))
      (node (ref "U3") (pin "4") (pinfunction "B_4") (pintype "passive"))
    )
    (net (code "4") (name "/LED_OUT_1") (class "Default")
      (node (ref "D10") (pin "3") (pinfunction "DO_3") (pintype "passive"))
      (node (ref "D11") (pin "2") (pinfunction "DI_2") (pintype "passive"))
    )
    (net (code "5") (name "/LED_OUT_2") (class "Default")
      (node (ref "D18") (pin "3") (pinfunction "DO_3") (pintype "passive"))
      (node (ref "D19") (pin "2") (pinfunction "DI_2") (pintype "passive"))
    )
    (net (code "6") (name "/LED_OUT_3") (class "Default")
      (node (ref "D26") (pin "3") (pinfunction "DO_3") (pintype "passive"))
      (node (ref "D27") (pin "2") (pinfunction "DI_2") (pintype "passive"))
    )
    (net (code "7") (name "/LED_OUT_4") (class "Default")
      (node (ref "D34") (pin "3") (pinfunction "DO_3") (pintype "passive"))
      (node (ref "D35") (pin "2") (pinfunction "DI_2") (pintype "passive"))
    )
    (net (code "8") (name "/LED_OUT_5") (class "Default")
      (node (ref "D42") (pin "3") (pinfunction "DO_3") (pintype "passive"))
      (node (ref "D43") (pin "2") (pinfunction "DI_2") (pintype "passive"))
    )
    (net (code "9") (name "/LED_OUT_6") (class "Default")
      (node (ref "D50") (pin "3") (pinfunction "DO_3") (pintype "passive"))
      (node (ref "D51") (pin "2") (pinfunction "DI_2") (pintype "passive"))
    )
    (net (code "10") (name "/LED_OUT_7") (class "Default")
      (node (ref "D58") (pin "3") (pinfunction "DO_3") (pintype "passive"))
      (node (ref "D59") (pin "2") (pinfunction "DI_2") (pintype "passive"))
    )
    (net (code "11") (name "/MCU_LED_DIN") (class "Default")
      (node (ref "U3") (pin "3") (pinfunction "A_3") (pintype "passive"))
    )
    (net (code "12") (name "GND") (class "Default")
      (node (ref "C10") (pin "1") (pinfunction "1_1") (pintype "passive"))
      (node (ref "C11") (pin "1") (pinfunction "1_1") (pintype "passive"))
      (node (ref "C12") (pin "1") (pinfunction "1_1") (pintype "passive"))
      (node (ref "C13") (pin "1") (pinfunction "1_1") (pintype "passive"))
      (node (ref "C14") (pin "1") (pinfunction "1_1") (pintype "passive"))
      (node (ref "C15") (pin "1") (pinfunction "1_1") (pintype "passive"))
      (node (ref "C16") (pin "1") (pinfunction "1_1") (pintype "passive"))
      (node (ref "C17") (pin "1") (pinfunction "1_1") (pintype "passive"))
      (node (ref "C18") (pin "1") (pinfunction "1_1") (pintype "passive"))
      (node (ref "C19") (pin "1") (pinfunction "1_1") (pintype "passive"))
      (node (ref "C20") (pin "1") (pinfunction "1_1") (pintype "passive"))
      (node (ref "C21") (pin "1") (pinfunction "1_1") (pintype "passive"))
      (node (ref "C22") (pin "1") (pinfunction "1_1") (pintype "passive"))
      (node (ref "C23") (pin "1") (pinfunction "1_1") (pintype "passive"))
      (node (ref "C24") (pin "1") (pinfunction "1_1") (pintype "passive"))
      (node (ref "C25") (pin "1") (pinfunction "1_1") (pintype "passive"))
      (node (ref "C26") (pin "1") (pinfunction "1_1") (pintype "passive"))
      (node (ref "C27") (pin "1") (pinfunction "1_1") (pintype "passive"))
      (node (ref "C28") (pin "1") (pinfunction "1_1") (pintype "passive"))
      (node (ref "C29") (pin "1") (pinfunction "1_1") (pintype "passive"))
      (node (ref "C30") (pin "1") (pinfunction "1_1") (pintype "passive"))
      (node (ref "C31") (pin "1") (pinfunction "1_1") (pintype "passive"))
      (node (ref "C32") (pin "1") (pinfunction "1_1") (pintype "passive"))
      (node (ref "C33") (pin "1") (pinfunction "1_1") (pintype "passive"))
      (node (ref "C34") (pin "1") (pinfunction "1_1") (pintype "passive"))
      (node (ref "C35") (pin "1") (pinfunction "1_1") (pintype "passive"))
      (node (ref "C36") (pin "1") (pinfunction "1_1") (pintype "passive"))
      (node (ref "C37") (pin "1") (pinfunction "1_1") (pintype "passive"))
      (node (ref "C38") (pin "1") (pinfunction "1_1") (pintype "passive"))
      (node (ref "C39") (pin "1") (pinfunction "1_1") (pintype "passive"))
      (node (ref "C40") (pin "1") (pinfunction "1_1") (pintype "passive"))
      (node (ref "C41") (pin "1") (pinfunction "1_1") (pintype "passive"))
      (node (ref "C42") (pin "1") (pinfunction "1_1") (pintype "passive"))
      (node (ref "C43") (pin "1") (pinfunction "1_1") (pintype "passive"))
      (node (ref "C44") (pin "1") (pinfunction "1_1") (pintype "passive"))
      (node (ref "C45") (pin "1") (pinfunction "1_1") (pintype "passive"))
      (node (ref "C46") (pin "1") (pinfunction "1_1") (pintype "passive"))
      (node (ref "C47") (pin "1") (pinfunction "1_1") (pintype "passive"))
      (node (ref "C48") (pin "1") (pinfunction "1_1") (pintype "passive"))
      (node (ref "C49") (pin "1") (pinfunction "1_1") (pintype "passive"))
      (node (ref "C50") (pin "1") (pinfunction "1_1") (pintype "passive"))
      (node (ref "C51") (pin "1") (pinfunction "1_1") (pintype "passive"))
      (node (ref "C52") (pin "1") (pinfunction "1_1") (pintype "passive"))
      (node (ref "C53") (pin "1") (pinfunction "1_1") (pintype "passive"))
      (node (ref "C54") (pin "1") (pinfunction "1_1") (pintype "passive"))
      (node (ref "C55") (pin "1") (pinfunction "1_1") (pintype "passive"))
      (node (ref "C56") (pin "1") (pinfunction "1_1") (pintype "passive"))
      (node (ref "C57") (pin "1") (pinfunction "1_1") (pintype "passive"))
      (node (ref "C58") (pin "1") (pinfunction "1_1") (pintype "passive"))
      (node (ref "C59") (pin "1") (pinfunction "1_1") (pintype "passive"))
      (node (ref "C6") (pin "1") (pinfunction "1_1") (pintype "passive"))
      (node (ref "C60") (pin "1") (pinfunction "1_1") (pintype "passive"))
      (node (ref "C61") (pin "1") (pinfunction "1_1") (pintype "passive"))
      (node (ref "C62") (pin "1") (pinfunction "1_1") (pintype "passive"))
      (node (ref "C63") (pin "1") (pinfunction "1_1") (pintype "passive"))
      (node (ref "C64") (pin "1") (pinfunction "1_1") (pintype "passive"))
      (node (ref "C65") (pin "1") (pinfunction "1_1") (pintype "passive"))
      (node (ref "C66") (pin "1") (pinfunction "1_1") (pintype "passive"))
      (node (ref "C67") (pin "1") (pinfunction "1_1") (pintype "passive"))
      (node (ref "C68") (pin "1") (pinfunction "1_1") (pintype "passive"))
      (node (ref "C69") (pin "1") (pinfunction "1_1") (pintype "passive"))
      (node (ref "C7") (pin "1") (pinfunction "1_1") (pintype "passive"))
      (node (ref "C70") (pin "1") (pinfunction "1_1") (pintype "passive"))
      (node (ref "C8") (pin "1") (pinfunction "1_1") (pintype "passive"))
      (node (ref "C9") (pin "1") (pinfunction "1_1") (pintype "passive"))
      (node (ref "D10") (pin "4") (pinfunction "GND_4") (pintype "passive"))
      (node (ref "D11") (pin "4") (pinfunction "GND_4") (pintype "passive"))
      (node (ref "D12") (pin "4") (pinfunction "GND_4") (pintype "passive"))
      (node (ref "D13") (pin "4") (pinfunction "GND_4") (pintype "passive"))
      (node (ref "D14") (pin "4") (pinfunction "GND_4") (pintype "passive"))
      (node (ref "D15") (pin "4") (pinfunction "GND_4") (pintype "passive"))
      (node (ref "D16") (pin "4") (pinfunction "GND_4") (pintype "passive"))
      (node (ref "D17") (pin "4") (pinfunction "GND_4") (pintype "passive"))
      (node (ref "D18") (pin "4") (pinfunction "GND_4") (pintype "passive"))
      (node (ref "D19") (pin "4") (pinfunction "GND_4") (pintype "passive"))
      (node (ref "D20") (pin "4") (pinfunction "GND_4") (pintype "passive"))
      (node (ref "D21") (pin "4") (pinfunction "GND_4") (pintype "passive"))
      (node (ref "D22") (pin "4") (pinfunction "GND_4") (pintype "passive"))
      (node (ref "D23") (pin "4") (pinfunction "GND_4") (pintype "passive"))
      (node (ref "D24") (pin "4") (pinfunction "GND_4") (pintype "passive"))
      (node (ref "D25") (pin "4") (pinfunction "GND_4") (pintype "passive"))
      (node (ref "D26") (pin "4") (pinfunction "GND_4") (pintype "passive"))
      (node (ref "D27") (pin "4") (pinfunction "GND_4") (pintype "passive"))
      (node (ref "D28") (pin "4") (pinfunction "GND_4") (pintype "passive"))
      (node (ref "D29") (pin "4") (pinfunction "GND_4") (pintype "passive"))
      (node (ref "D3") (pin "4") (pinfunction "GND_4") (pintype "passive"))
      (node (ref "D30") (pin "4") (pinfunction "GND_4") (pintype "passive"))
      (node (ref "D31") (pin "4") (pinfunction "GND_4") (pintype "passive"))
      (node (ref "D32") (pin "4") (pinfunction "GND_4") (pintype "passive"))
      (node (ref "D33") (pin "4") (pinfunction "GND_4") (pintype "passive"))
      (node (ref "D34") (pin "4") (pinfunction "GND_4") (pintype "passive"))
      (node (ref "D35") (pin "4") (pinfunction "GND_4") (pintype "passive"))
      (node (ref "D36") (pin "4") (pinfunction "GND_4") (pintype "passive"))
      (node (ref "D37") (pin "4") (pinfunction "GND_4") (pintype "passive"))
      (node (ref "D38") (pin "4") (pinfunction "GND_4") (pintype "passive"))
      (node (ref "D39") (pin "4") (pinfunction "GND_4") (pintype "passive"))
      (node (ref "D4") (pin "4") (pinfunction "GND_4") (pintype "passive"))
      (node (ref "D40") (pin "4") (pinfunction "GND_4") (pintype "passive"))
      (node (ref "D41") (pin "4") (pinfunction "GND_4") (pintype "passive"))
      (node (ref "D42") (pin "4") (pinfunction "GND_4") (pintype "passive"))
      (node (ref "D43") (pin "4") (pinfunction "GND_4") (pintype "passive"))
      (node (ref "D44") (pin "4") (pinfunction "GND_4") (pintype "passive"))
      (node (ref "D45") (pin "4") (pinfunction "GND_4") (pintype "passive"))
      (node (ref "D46") (pin "4") (pinfunction "GND_4") (pintype "passive"))
      (node (ref "D47") (pin "4") (pinfunction "GND_4") (pintype "passive"))
      (node (ref "D48") (pin "4") (pinfunction "GND_4") (pintype "passive"))
      (node (ref "D49") (pin "4") (pinfunction "GND_4") (pintype "passive"))
      (node (ref "D5") (pin "4") (pinfunction "GND_4") (pintype "passive"))
      (node (ref "D50") (pin "4") (pinfunction "GND_4") (pintype "passive"))
      (node (ref "D51") (pin "4") (pinfunction "GND_4") (pintype "passive"))
      (node (ref "D52") (pin "4") (pinfunction "GND_4") (pintype "passive"))
      (node (ref "D53") (pin "4") (pinfunction "GND_4") (pintype "passive"))
      (node (ref "D54") (pin "4") (pinfunction "GND_4") (pintype "passive"))
      (node (ref "D55") (pin "4") (pinfunction "GND_4") (pintype "passive"))
      (node (ref "D56") (pin "4") (pinfunction "GND_4") (pintype "passive"))
      (node (ref "D57") (pin "4") (pinfunction "GND_4") (pintype "passive"))
      (node (ref "D58") (pin "4") (pinfunction "GND_4") (pintype "passive"))
      (node (ref "D59") (pin "4") (pinfunction "GND_4") (pintype "passive"))
      (node (ref "D6") (pin "4") (pinfunction "GND_4") (pintype "passive"))
      (node (ref "D60") (pin "4") (pinfunction "GND_4") (pintype "passive"))
      (node (ref "D61") (pin "4") (pinfunction "GND_4") (pintype "passive"))
      (node (ref "D62") (pin "4") (pinfunction "GND_4") (pintype "passive"))
      (node (ref "D63") (pin "4") (pinfunction "GND_4") (pintype "passive"))
      (node (ref "D64") (pin "4") (pinfunction "GND_4") (pintype "passive"))
      (node (ref "D65") (pin "4") (pinfunction "GND_4") (pintype "passive"))
      (node (ref "D66") (pin "4") (pinfunction "GND_4") (pintype "passive"))
      (node (ref "D7") (pin "4") (pinfunction "GND_4") (pintype "passive"))
      (node (ref "D8") (pin "4") (pinfunction "GND_4") (pintype "passive"))
      (node (ref "D9") (pin "4") (pinfunction "GND_4") (pintype "passive"))
      (node (ref "U3") (pin "2") (pinfunction "GND_2") (pintype "passive"))
    )
    (net (code "13") (name "Net-(D3-DO)") (class "Default")
      (node (ref "D3") (pin "3") (pinfunction "DO_3") (pintype "passive"))
      (node (ref "D4") (pin "2") (pinfunction "DI_2") (pintype "passive"))
    )
    (net (code "14") (name "Net-(D4-DO)") (class "Default")
      (node (ref "D4") (pin "3") (pinfunction "DO_3") (pintype "passive"))
      (node (ref "D5") (pin "2") (pinfunction "DI_2") (pintype "passive"))
    )
    (net (code "15") (name "Net-(D5-DO)") (class "Default")
      (node (ref "D5") (pin "3") (pinfunction "DO_3") (pintype "passive"))
      (node (ref "D6") (pin "2") (pinfunction "DI_2") (pintype "passive"))
    )
    (net (code "16") (name "Net-(D6-DO)") (class "Default")
      (node (ref "D6") (pin "3") (pinfunction "DO_3") (pintype "passive"))
      (node (ref "D7") (pin "2") (pinfunction "DI_2") (pintype "passive"))
    )
    (net (code "17") (name "Net-(D7-DO)") (class "Default")
      (node (ref "D7") (pin "3") (pinfunction "DO_3") (pintype "passive"))
      (node (ref "D8") (pin "2") (pinfunction "DI_2") (pintype "passive"))
    )
    (net (code "18") (name "Net-(D8-DO)") (class "Default")
      (node (ref "D8") (pin "3") (pinfunction "DO_3") (pintype "passive"))
      (node (ref "D9") (pin "2") (pinfunction "DI_2") (pintype "passive"))
    )
    (net (code "19") (name "Net-(D10-DI)") (class "Default")
      (node (ref "D10") (pin "2") (pinfunction "DI_2") (pintype "passive"))
      (node (ref "D9") (pin "3") (pinfunction "DO_3") (pintype "passive"))
    )
    (net (code "20") (name "Net-(D11-DO)") (class "Default")
      (node (ref "D11") (pin "3") (pinfunction "DO_3") (pintype "passive"))
      (node (ref "D12") (pin "2") (pinfunction "DI_2") (pintype "passive"))
    )
    (net (code "21") (name "Net-(D12-DO)") (class "Default")
      (node (ref "D12") (pin "3") (pinfunction "DO_3") (pintype "passive"))
      (node (ref "D13") (pin "2") (pinfunction "DI_2") (pintype "passive"))
    )
    (net (code "22") (name "Net-(D13-DO)") (class "Default")
      (node (ref "D13") (pin "3") (pinfunction "DO_3") (pintype "passive"))
      (node (ref "D14") (pin "2") (pinfunction "DI_2") (pintype "passive"))
    )
    (net (code "23") (name "Net-(D14-DO)") (class "Default")
      (node (ref "D14") (pin "3") (pinfunction "DO_3") (pintype "passive"))
      (node (ref "D15") (pin "2") (pinfunction "DI_2") (pintype "passive"))
    )
    (net (code "24") (name "Net-(D15-DO)") (class "Default")
      (node (ref "D15") (pin "3") (pinfunction "DO_3") (pintype "passive"))
      (node (ref "D16") (pin "2") (pinfunction "DI_2") (pintype "passive"))
    )
    (net (code "25") (name "Net-(D16-DO)") (class "Default")
      (node (ref "D16") (pin "3") (pinfunction "DO_3") (pintype "passive"))
      (node (ref "D17") (pin "2") (pinfunction "DI_2") (pintype "passive"))
    )
    (net (code "26") (name "Net-(D17-DO)") (class "Default")
      (node (ref "D17") (pin "3") (pinfunction "DO_3") (pintype "passive"))
      (node (ref "D18") (pin "2") (pinfunction "DI_2") (pintype "passive"))
    )
    (net (code "27") (name "Net-(D19-DO)") (class "Default")
      (node (ref "D19") (pin "3") (pinfunction "DO_3") (pintype "passive"))
      (node (ref "D20") (pin "2") (pinfunction "DI_2") (pintype "passive"))
    )
    (net (code "28") (name "Net-(D20-DO)") (class "Default")
      (node (ref "D20") (pin "3") (pinfunction "DO_3") (pintype "passive"))
      (node (ref "D21") (pin "2") (pinfunction "DI_2") (pintype "passive"))
    )
    (net (code "29") (name "Net-(D21-DO)") (class "Default")
      (node (ref "D21") (pin "3") (pinfunction "DO_3") (pintype "passive"))
      (node (ref "D22") (pin "2") (pinfunction "DI_2") (pintype "passive"))
    )
    (net (code "30") (name "Net-(D22-DO)") (class "Default")
      (node (ref "D22") (pin "3") (pinfunction "DO_3") (pintype "passive"))
      (node (ref "D23") (pin "2") (pinfunction "DI_2") (pintype "passive"))
    )
    (net (code "31") (name "Net-(D23-DO)") (class "Default")
      (node (ref "D23") (pin "3") (pinfunction "DO_3") (pintype "passive"))
      (node (ref "D24") (pin "2") (pinfunction "DI_2") (pintype "passive"))
    )
    (net (code "32") (name "Net-(D24-DO)") (class "Default")
      (node (ref "D24") (pin "3") (pinfunction "DO_3") (pintype "passive"))
      (node (ref "D25") (pin "2") (pinfunction "DI_2") (pintype "passive"))
    )
    (net (code "33") (name "Net-(D25-DO)") (class "Default")
      (node (ref "D25") (pin "3") (pinfunction "DO_3") (pintype "passive"))
      (node (ref "D26") (pin "2") (pinfunction "DI_2") (pintype "passive"))
    )
    (net (code "34") (name "Net-(D27-DO)") (class "Default")
      (node (ref "D27") (pin "3") (pinfunction "DO_3") (pintype "passive"))
      (node (ref "D28") (pin "2") (pinfunction "DI_2") (pintype "passive"))
    )
    (net (code "35") (name "Net-(D28-DO)") (class "Default")
      (node (ref "D28") (pin "3") (pinfunction "DO_3") (pintype "passive"))
      (node (ref "D29") (pin "2") (pinfunction "DI_2") (pintype "passive"))
    )
    (net (code "36") (name "Net-(D29-DO)") (class "Default")
      (node (ref "D29") (pin "3") (pinfunction "DO_3") (pintype "passive"))
      (node (ref "D30") (pin "2") (pinfunction "DI_2") (pintype "passive"))
    )
    (net (code "37") (name "Net-(D30-DO)") (class "Default")
      (node (ref "D30") (pin "3") (pinfunction "DO_3") (pintype "passive"))
      (node (ref "D31") (pin "2") (pinfunction "DI_2") (pintype "passive"))
    )
    (net (code "38") (name "Net-(D31-DO)") (class "Default")
      (node (ref "D31") (pin "3") (pinfunction "DO_3") (pintype "passive"))
      (node (ref "D32") (pin "2") (pinfunction "DI_2") (pintype "passive"))
    )
    (net (code "39") (name "Net-(D32-DO)") (class "Default")
      (node (ref "D32") (pin "3") (pinfunction "DO_3") (pintype "passive"))
      (node (ref "D33") (pin "2") (pinfunction "DI_2") (pintype "passive"))
    )
    (net (code "40") (name "Net-(D33-DO)") (class "Default")
      (node (ref "D33") (pin "3") (pinfunction "DO_3") (pintype "passive"))
      (node (ref "D34") (pin "2") (pinfunction "DI_2") (pintype "passive"))
    )
    (net (code "41") (name "Net-(D35-DO)") (class "Default")
      (node (ref "D35") (pin "3") (pinfunction "DO_3") (pintype "passive"))
      (node (ref "D36") (pin "2") (pinfunction "DI_2") (pintype "passive"))
    )
    (net (code "42") (name "Net-(D36-DO)") (class "Default")
      (node (ref "D36") (pin "3") (pinfunction "DO_3") (pintype "passive"))
      (node (ref "D37") (pin "2") (pinfunction "DI_2") (pintype "passive"))
    )
    (net (code "43") (name "Net-(D37-DO)") (class "Default")
      (node (ref "D37") (pin "3") (pinfunction "DO_3") (pintype "passive"))
      (node (ref "D38") (pin "2") (pinfunction "DI_2") (pintype "passive"))
    )
    (net (code "44") (name "Net-(D38-DO)") (class "Default")
      (node (ref "D38") (pin "3") (pinfunction "DO_3") (pintype "passive"))
      (node (ref "D39") (pin "2") (pinfunction "DI_2") (pintype "passive"))
    )
    (net (code "45") (name "Net-(D39-DO)") (class "Default")
      (node (ref "D39") (pin "3") (pinfunction "DO_3") (pintype "passive"))
      (node (ref "D40") (pin "2") (pinfunction "DI_2") (pintype "passive"))
    )
    (net (code "46") (name "Net-(D40-DO)") (class "Default")
      (node (ref "D40") (pin "3") (pinfunction "DO_3") (pintype "passive"))
      (node (ref "D41") (pin "2") (pinfunction "DI_2") (pintype "passive"))
    )
    (net (code "47") (name "Net-(D41-DO)") (class "Default")
      (node (ref "D41") (pin "3") (pinfunction "DO_3") (pintype "passive"))
      (node (ref "D42") (pin "2") (pinfunction "DI_2") (pintype "passive"))
    )
    (net (code "48") (name "Net-(D43-DO)") (class "Default")
      (node (ref "D43") (pin "3") (pinfunction "DO_3") (pintype "passive"))
      (node (ref "D44") (pin "2") (pinfunction "DI_2") (pintype "passive"))
    )
    (net (code "49") (name "Net-(D44-DO)") (class "Default")
      (node (ref "D44") (pin "3") (pinfunction "DO_3") (pintype "passive"))
      (node (ref "D45") (pin "2") (pinfunction "DI_2") (pintype "passive"))
    )
    (net (code "50") (name "Net-(D45-DO)") (class "Default")
      (node (ref "D45") (pin "3") (pinfunction "DO_3") (pintype "passive"))
      (node (ref "D46") (pin "2") (pinfunction "DI_2") (pintype "passive"))
    )
    (net (code "51") (name "Net-(D46-DO)") (class "Default")
      (node (ref "D46") (pin "3") (pinfunction "DO_3") (pintype "passive"))
      (node (ref "D47") (pin "2") (pinfunction "DI_2") (pintype "passive"))
    )
    (net (code "52") (name "Net-(D47-DO)") (class "Default")
      (node (ref "D47") (pin "3") (pinfunction "DO_3") (pintype "passive"))
      (node (ref "D48") (pin "2") (pinfunction "DI_2") (pintype "passive"))
    )
    (net (code "53") (name "Net-(D48-DO)") (class "Default")
      (node (ref "D48") (pin "3") (pinfunction "DO_3") (pintype "passive"))
      (node (ref "D49") (pin "2") (pinfunction "DI_2") (pintype "passive"))
    )
    (net (code "54") (name "Net-(D49-DO)") (class "Default")
      (node (ref "D49") (pin "3") (pinfunction "DO_3") (pintype "passive"))
      (node (ref "D50") (pin "2") (pinfunction "DI_2") (pintype "passive"))
    )
    (net (code "55") (name "Net-(D51-DO)") (class "Default")
      (node (ref "D51") (pin "3") (pinfunction "DO_3") (pintype "passive"))
      (node (ref "D52") (pin "2") (pinfunction "DI_2") (pintype "passive"))
    )
    (net (code "56") (name "Net-(D52-DO)") (class "Default")
      (node (ref "D52") (pin "3") (pinfunction "DO_3") (pintype "passive"))
      (node (ref "D53") (pin "2") (pinfunction "DI_2") (pintype "passive"))
    )
    (net (code "57") (name "Net-(D53-DO)") (class "Default")
      (node (ref "D53") (pin "3") (pinfunction "DO_3") (pintype "passive"))
      (node (ref "D54") (pin "2") (pinfunction "DI_2") (pintype "passive"))
    )
    (net (code "58") (name "Net-(D54-DO)") (class "Default")
      (node (ref "D54") (pin "3") (pinfunction "DO_3") (pintype "passive"))
      (node (ref "D55") (pin "2") (pinfunction "DI_2") (pintype "passive"))
    )
    (net (code "59") (name "Net-(D55-DO)") (class "Default")
      (node (ref "D55") (pin "3") (pinfunction "DO_3") (pintype "passive"))
      (node (ref "D56") (pin "2") (pinfunction "DI_2") (pintype "passive"))
    )
    (net (code "60") (name "Net-(D56-DO)") (class "Default")
      (node (ref "D56") (pin "3") (pinfunction "DO_3") (pintype "passive"))
      (node (ref "D57") (pin "2") (pinfunction "DI_2") (pintype "passive"))
    )
    (net (code "61") (name "Net-(D57-DO)") (class "Default")
      (node (ref "D57") (pin "3") (pinfunction "DO_3") (pintype "passive"))
      (node (ref "D58") (pin "2") (pinfunction "DI_2") (pintype "passive"))
    )
    (net (code "62") (name "Net-(D59-DO)") (class "Default")
      (node (ref "D59") (pin "3") (pinfunction "DO_3") (pintype "passive"))
      (node (ref "D60") (pin "2") (pinfunction "DI_2") (pintype "passive"))
    )
    (net (code "63") (name "Net-(D60-DO)") (class "Default")
      (node (ref "D60") (pin "3") (pinfunction "DO_3") (pintype "passive"))
      (node (ref "D61") (pin "2") (pinfunction "DI_2") (pintype "passive"))
    )
    (net (code "64") (name "Net-(D61-DO)") (class "Default")
      (node (ref "D61") (pin "3") (pinfunction "DO_3") (pintype "passive"))
      (node (ref "D62") (pin "2") (pinfunction "DI_2") (pintype "passive"))
    )
    (net (code "65") (name "Net-(D62-DO)") (class "Default")
      (node (ref "D62") (pin "3") (pinfunction "DO_3") (pintype "passive"))
      (node (ref "D63") (pin "2") (pinfunction "DI_2") (pintype "passive"))
    )
    (net (code "66") (name "Net-(D63-DO)") (class "Default")
      (node (ref "D63") (pin "3") (pinfunction "DO_3") (pintype "passive"))
      (node (ref "D64") (pin "2") (pinfunction "DI_2") (pintype "passive"))
    )
    (net (code "67") (name "Net-(D64-DO)") (class "Default")
      (node (ref "D64") (pin "3") (pinfunction "DO_3") (pintype "passive"))
      (node (ref "D65") (pin "2") (pinfunction "DI_2") (pintype "passive"))
    )
    (net (code "68") (name "Net-(D65-DO)") (class "Default")
      (node (ref "D65") (pin "3") (pinfunction "DO_3") (pintype "passive"))
      (node (ref "D66") (pin "2") (pinfunction "DI_2") (pintype "passive"))
    )
    (net (code "69") (name "unconnected-(D66-DO-Pad3)") (class "Default")
      (node (ref "D66") (pin "3") (pinfunction "DO_3") (pintype "passive+no_connect"))
    )
  )
)
